# Sonar_Amp_Sheet.net
KiCad netlist of a schematic drawn in Altium Designer
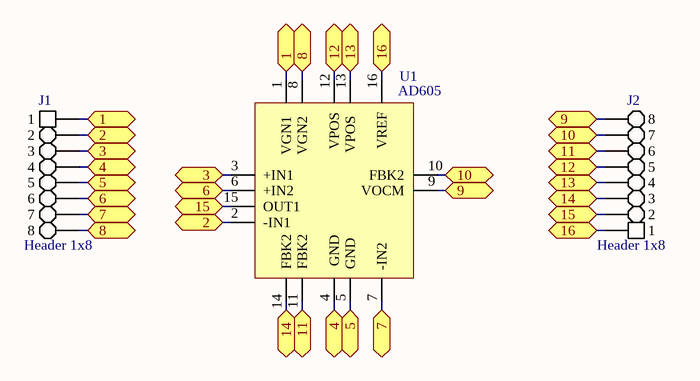
[diagram p0: Sonar_Amp_Sheet.SchDoc]

(export (version "E")
  (design (tool "Eeschema 10.0.6"))
  (components
    (comp (ref "J1")
      (value "Header 1x8")
      (footprint "Header 1x8")
      (description "Header")
      (libsource (lib "Sonar_Amp__Schlib") (part "Header 1x8"))
    )
    (comp (ref "J2")
      (value "Header 1x8")
      (footprint "Header 1x8")
      (description "Header")
      (libsource (lib "Sonar_Amp__Schlib") (part "Header 1x8"))
    )
    (comp (ref "U1")
      (value "AD605")
      (footprint "SOIC127P600X175-16N")
      (libsource (lib "Sonar_Amp__Schlib") (part "AD605"))
    )
  )
  (nets
    (net (code "1") (name "/1") (class "Default")
      (node (ref "J1") (pin "1") (pinfunction "1_1") (pintype "passive"))
      (node (ref "U1") (pin "1") (pinfunction "VGN1_1") (pintype "passive"))
    )
    (net (code "2") (name "/2") (class "Default")
      (node (ref "J1") (pin "2") (pinfunction "2_2") (pintype "passive"))
      (node (ref "U1") (pin "2") (pinfunction "-IN1_2") (pintype "passive"))
    )
    (net (code "3") (name "/3") (class "Default")
      (node (ref "J1") (pin "3") (pinfunction "3_3") (pintype "passive"))
      (node (ref "U1") (pin "3") (pinfunction "+IN1_3") (pintype "passive"))
    )
    (net (code "4") (name "/4") (class "Default")
      (node (ref "J1") (pin "4") (pinfunction "4_4") (pintype "passive"))
      (node (ref "U1") (pin "4") (pinfunction "GND_4") (pintype "passive"))
    )
    (net (code "5") (name "/5") (class "Default")
      (node (ref "J1") (pin "5") (pinfunction "5_5") (pintype "passive"))
      (node (ref "U1") (pin "5") (pinfunction "GND_5") (pintype "passive"))
    )
    (net (code "6") (name "/6") (class "Default")
      (node (ref "J1") (pin "6") (pinfunction "6_6") (pintype "passive"))
      (node (ref "U1") (pin "6") (pinfunction "+IN2_6") (pintype "passive"))
    )
    (net (code "7") (name "/7") (class "Default")
      (node (ref "J1") (pin "7") (pinfunction "7_7") (pintype "passive"))
      (node (ref "U1") (pin "7") (pinfunction "-IN2_7") (pintype "passive"))
    )
    (net (code "8") (name "/8") (class "Default")
      (node (ref "J1") (pin "8") (pinfunction "8_8") (pintype "passive"))
      (node (ref "U1") (pin "8") (pinfunction "VGN2_8") (pintype "passive"))
    )
    (net (code "9") (name "/9") (class "Default")
      (node (ref "J2") (pin "8") (pinfunction "8_8") (pintype "passive"))
      (node (ref "U1") (pin "9") (pinfunction "VOCM_9") (pintype "passive"))
    )
    (net (code "10") (name "/10") (class "Default")
      (node (ref "J2") (pin "7") (pinfunction "7_7") (pintype "passive"))
      (node (ref "U1") (pin "10") (pinfunction "FBK2_10") (pintype "passive"))
    )
    (net (code "11") (name "/11") (class "Default")
      (node (ref "J2") (pin "6") (pinfunction "6_6") (pintype "passive"))
      (node (ref "U1") (pin "11") (pinfunction "FBK2_11") (pintype "passive"))
    )
    (net (code "12") (name "/12") (class "Default")
      (node (ref "J2") (pin "5") (pinfunction "5_5") (pintype "passive"))
      (node (ref "U1") (pin "12") (pinfunction "VPOS_12") (pintype "passive"))
    )
    (net (code "13") (name "/13") (class "Default")
      (node (ref "J2") (pin "4") (pinfunction "4_4") (pintype "passive"))
      (node (ref "U1") (pin "13") (pinfunction "VPOS_13") (pintype "passive"))
    )
    (net (code "14") (name "/14") (class "Default")
      (node (ref "J2") (pin "3") (pinfunction "3_3") (pintype "passive"))
      (node (ref "U1") (pin "14") (pinfunction "FBK2_14") (pintype "passive"))
    )
    (net (code "15") (name "/15") (class "Default")
      (node (ref "J2") (pin "2") (pinfunction "2_2") (pintype "passive"))
      (node (ref "U1") (pin "15") (pinfunction "OUT1_15") (pintype "passive"))
    )
    (net (code "16") (name "/16") (class "Default")
      (node (ref "J2") (pin "1") (pinfunction "1_1") (pintype "passive"))
      (node (ref "U1") (pin "16") (pinfunction "VREF_16") (pintype "passive"))
    )
  )
)
